# Board_1.net
KiCad netlist of a schematic drawn in EAGLE
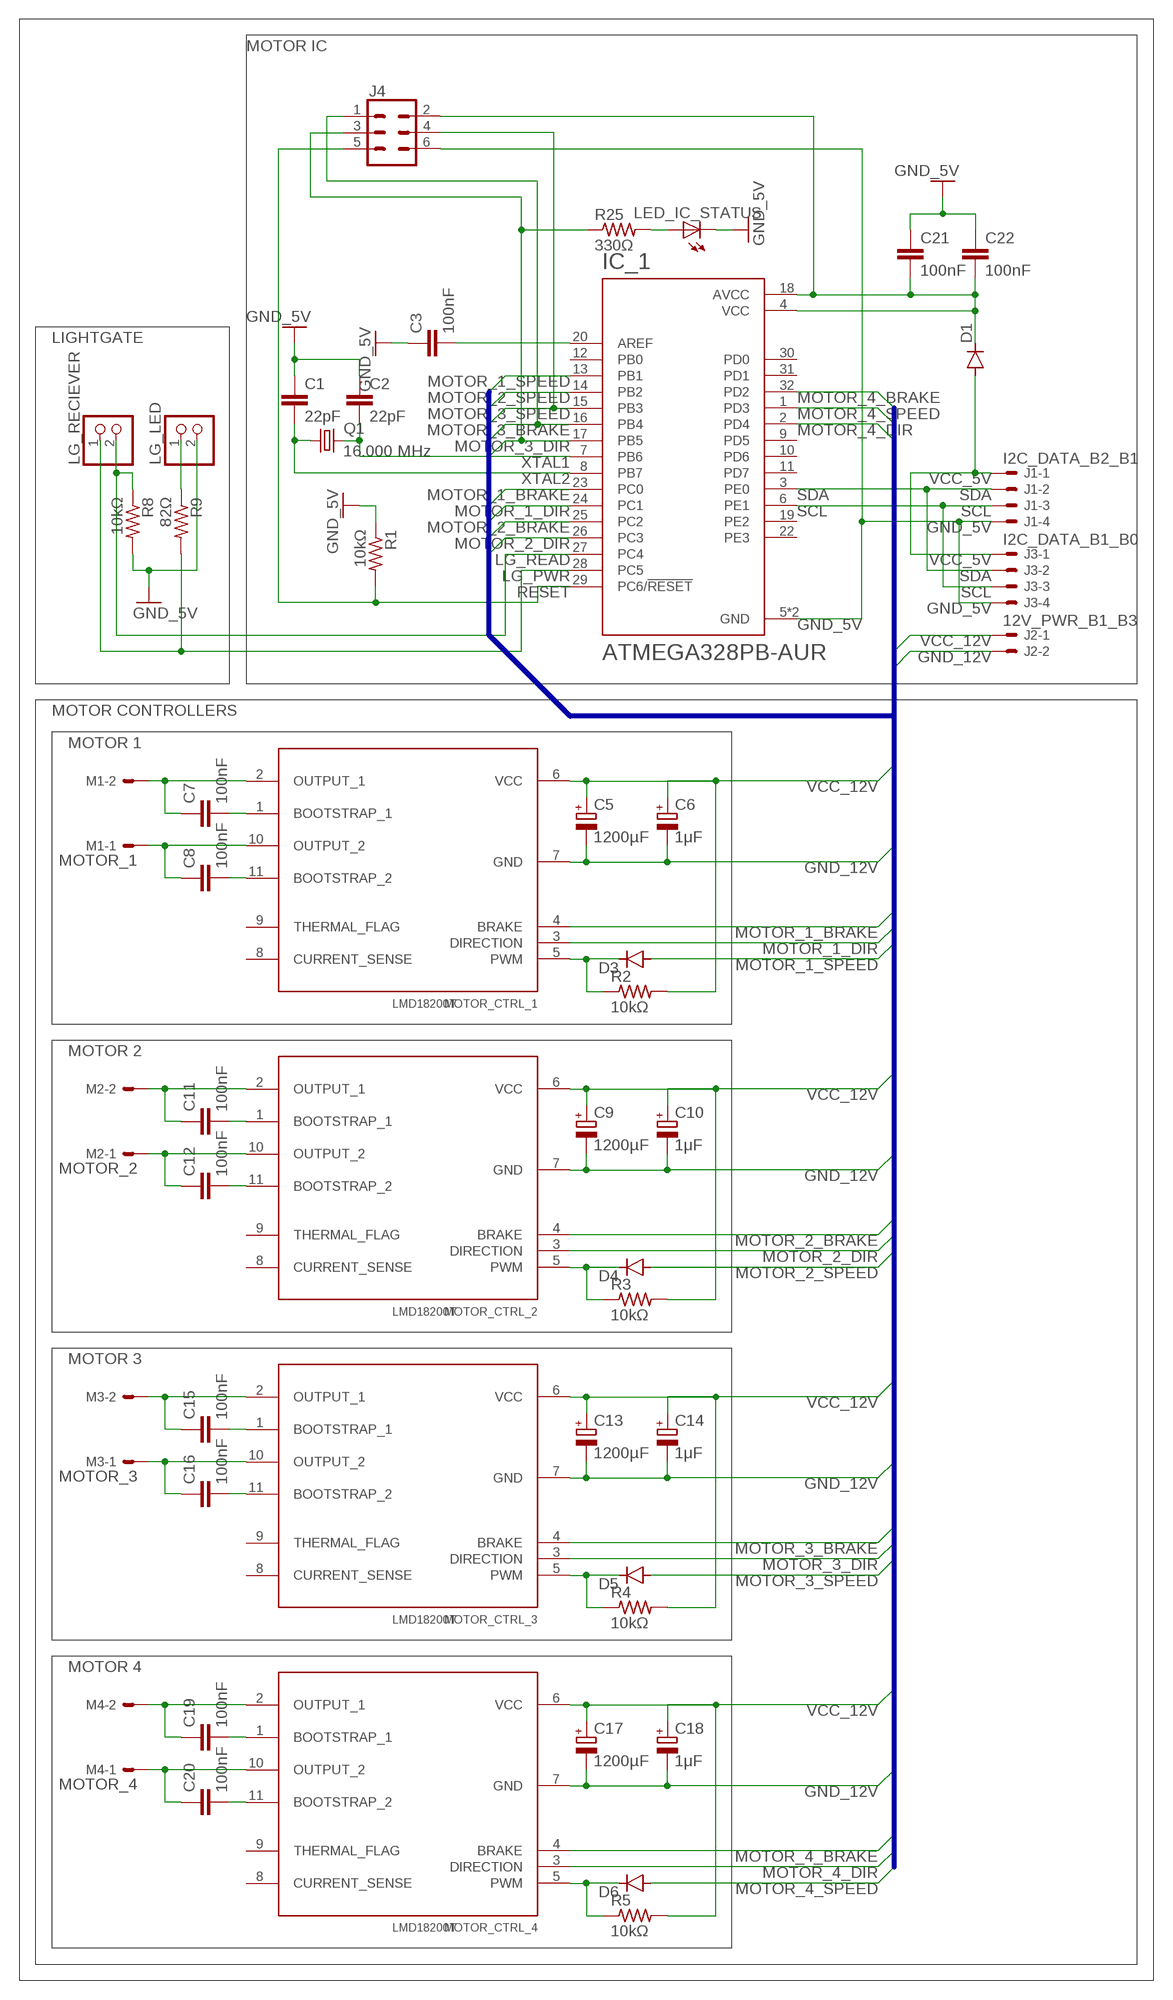
[diagram p0: schematic, sheet 1]

(export (version "E")
  (design (tool "Eeschema 10.0.6"))
  (components
    (comp (ref "C1")
      (value "22pF")
      (footprint "eagle-import:C050-024X044")
      (libsource (lib "eagle-import") (part "C-EU050-024X044"))
    )
    (comp (ref "C2")
      (value "22pF")
      (footprint "eagle-import:C050-024X044")
      (libsource (lib "eagle-import") (part "C-EU050-024X044"))
    )
    (comp (ref "C3")
      (value "100nF")
      (footprint "eagle-import:C050-024X044")
      (libsource (lib "eagle-import") (part "C-EU050-024X044"))
    )
    (comp (ref "C5")
      (value "1200µF")
      (footprint "eagle-import:E5-13")
      (libsource (lib "eagle-import") (part "CPOL-EUE5-13"))
    )
    (comp (ref "C6")
      (value "1μF")
      (footprint "eagle-import:E2-5")
      (libsource (lib "eagle-import") (part "CPOL-EUE2-5"))
    )
    (comp (ref "C7")
      (value "100nF")
      (footprint "eagle-import:C050-024X044")
      (libsource (lib "eagle-import") (part "C-EU050-024X044"))
    )
    (comp (ref "C8")
      (value "100nF")
      (footprint "eagle-import:C050-024X044")
      (libsource (lib "eagle-import") (part "C-EU050-024X044"))
    )
    (comp (ref "C9")
      (value "1200µF")
      (footprint "eagle-import:E5-13")
      (libsource (lib "eagle-import") (part "CPOL-EUE5-13"))
    )
    (comp (ref "C10")
      (value "1μF")
      (footprint "eagle-import:E2-5")
      (libsource (lib "eagle-import") (part "CPOL-EUE2-5"))
    )
    (comp (ref "C11")
      (value "100nF")
      (footprint "eagle-import:C050-024X044")
      (libsource (lib "eagle-import") (part "C-EU050-024X044"))
    )
    (comp (ref "C12")
      (value "100nF")
      (footprint "eagle-import:C050-024X044")
      (libsource (lib "eagle-import") (part "C-EU050-024X044"))
    )
    (comp (ref "C13")
      (value "1200µF")
      (footprint "eagle-import:E5-13")
      (libsource (lib "eagle-import") (part "CPOL-EUE5-13"))
    )
    (comp (ref "C14")
      (value "1μF")
      (footprint "eagle-import:E2-5")
      (libsource (lib "eagle-import") (part "CPOL-EUE2-5"))
    )
    (comp (ref "C15")
      (value "100nF")
      (footprint "eagle-import:C050-024X044")
      (libsource (lib "eagle-import") (part "C-EU050-024X044"))
    )
    (comp (ref "C16")
      (value "100nF")
      (footprint "eagle-import:C050-024X044")
      (libsource (lib "eagle-import") (part "C-EU050-024X044"))
    )
    (comp (ref "C17")
      (value "1200µF")
      (footprint "eagle-import:E5-13")
      (libsource (lib "eagle-import") (part "CPOL-EUE5-13"))
    )
    (comp (ref "C18")
      (value "1μF")
      (footprint "eagle-import:E2-5")
      (libsource (lib "eagle-import") (part "CPOL-EUE2-5"))
    )
    (comp (ref "C19")
      (value "100nF")
      (footprint "eagle-import:C050-024X044")
      (libsource (lib "eagle-import") (part "C-EU050-024X044"))
    )
    (comp (ref "C20")
      (value "100nF")
      (footprint "eagle-import:C050-024X044")
      (libsource (lib "eagle-import") (part "C-EU050-024X044"))
    )
    (comp (ref "C21")
      (value "100nF")
      (footprint "eagle-import:C050-024X044")
      (libsource (lib "eagle-import") (part "C-EU050-024X044"))
    )
    (comp (ref "C22")
      (value "100nF")
      (footprint "eagle-import:C050-024X044")
      (libsource (lib "eagle-import") (part "C-EU050-024X044"))
    )
    (comp (ref "D1")
      (value "1N4148DO35-7")
      (footprint "eagle-import:DO35-7")
      (libsource (lib "eagle-import") (part "1N4148DO35-7"))
    )
    (comp (ref "D3")
      (value "1N4148DO35-7")
      (footprint "eagle-import:DO35-7")
      (libsource (lib "eagle-import") (part "1N4148DO35-7"))
    )
    (comp (ref "D4")
      (value "1N4148DO35-7")
      (footprint "eagle-import:DO35-7")
      (libsource (lib "eagle-import") (part "1N4148DO35-7"))
    )
    (comp (ref "D5")
      (value "1N4148DO35-7")
      (footprint "eagle-import:DO35-7")
      (libsource (lib "eagle-import") (part "1N4148DO35-7"))
    )
    (comp (ref "D6")
      (value "1N4148DO35-7")
      (footprint "eagle-import:DO35-7")
      (libsource (lib "eagle-import") (part "1N4148DO35-7"))
    )
    (comp (ref "IC_1")
      (value "ATMEGA328PB-AUR")
      (footprint "eagle-import:QFP80P900X900X120-32N")
      (fields (field (name "MF") "Microchip"))
      (libsource (lib "eagle-import") (part "ATMEGA328PB-AUR"))
    )
    (comp (ref "J1")
      (value "I2C_DATA_B2_B1")
      (footprint "eagle-import:6410-04")
      (fields (field (name "MF") "MOLEX"))
      (libsource (lib "eagle-import") (part "22-?-0427-2041"))
    )
    (comp (ref "J2")
      (value "12V_PWR_B1_B3")
      (footprint "eagle-import:6410-02")
      (fields (field (name "MF") "MOLEX"))
      (libsource (lib "eagle-import") (part "22-?-0227-2021"))
    )
    (comp (ref "J3")
      (value "I2C_DATA_B1_B0")
      (footprint "eagle-import:6410-04")
      (fields (field (name "MF") "MOLEX"))
      (libsource (lib "eagle-import") (part "22-?-0427-2041"))
    )
    (comp (ref "J4")
      (value "CONN_03X2SHROUD")
      (footprint "eagle-import:2X3-SHROUDED")
      (libsource (lib "eagle-import") (part "CONN_03X2SHROUD"))
    )
    (comp (ref "LED_IC_STATUS")
      (value "LEDP-LCC-2")
      (footprint "eagle-import:P-LCC-2")
      (libsource (lib "eagle-import") (part "LEDP-LCC-2"))
    )
    (comp (ref "LG_LED")
      (value "PINHD-1X2")
      (footprint "eagle-import:1X02")
      (libsource (lib "eagle-import") (part "PINHD-1X2"))
    )
    (comp (ref "LG_RECIEVER")
      (value "PINHD-1X2")
      (footprint "eagle-import:1X02")
      (libsource (lib "eagle-import") (part "PINHD-1X2"))
    )
    (comp (ref "M1")
      (value "MOTOR_1")
      (footprint "eagle-import:6410-02")
      (fields (field (name "MF") "MOLEX"))
      (libsource (lib "eagle-import") (part "22-?-0227-2021"))
    )
    (comp (ref "M2")
      (value "MOTOR_2")
      (footprint "eagle-import:6410-02")
      (fields (field (name "MF") "MOLEX"))
      (libsource (lib "eagle-import") (part "22-?-0227-2021"))
    )
    (comp (ref "M3")
      (value "MOTOR_3")
      (footprint "eagle-import:6410-02")
      (fields (field (name "MF") "MOLEX"))
      (libsource (lib "eagle-import") (part "22-?-0227-2021"))
    )
    (comp (ref "M4")
      (value "MOTOR_4")
      (footprint "eagle-import:6410-02")
      (fields (field (name "MF") "MOLEX"))
      (libsource (lib "eagle-import") (part "22-?-0227-2021"))
    )
    (comp (ref "MOTOR_CTRL_1")
      (value "LMD18200T")
      (footprint "eagle-import:TO-220-11")
      (libsource (lib "eagle-import") (part "LMD18200T"))
    )
    (comp (ref "MOTOR_CTRL_2")
      (value "LMD18200T")
      (footprint "eagle-import:TO-220-11")
      (libsource (lib "eagle-import") (part "LMD18200T"))
    )
    (comp (ref "MOTOR_CTRL_3")
      (value "LMD18200T")
      (footprint "eagle-import:TO-220-11")
      (libsource (lib "eagle-import") (part "LMD18200T"))
    )
    (comp (ref "MOTOR_CTRL_4")
      (value "LMD18200T")
      (footprint "eagle-import:TO-220-11")
      (libsource (lib "eagle-import") (part "LMD18200T"))
    )
    (comp (ref "Q1")
      (value "16.000 MHz")
      (footprint "eagle-import:HC49U-V")
      (libsource (lib "eagle-import") (part "CRYSTALHC49U-V"))
    )
    (comp (ref "R1")
      (value "10kΩ")
      (footprint "eagle-import:0207_10")
      (libsource (lib "eagle-import") (part "R-US_0207/10"))
    )
    (comp (ref "R2")
      (value "10kΩ")
      (footprint "eagle-import:0207_10")
      (libsource (lib "eagle-import") (part "R-US_0207/10"))
    )
    (comp (ref "R3")
      (value "10kΩ")
      (footprint "eagle-import:0207_10")
      (libsource (lib "eagle-import") (part "R-US_0207/10"))
    )
    (comp (ref "R4")
      (value "10kΩ")
      (footprint "eagle-import:0207_10")
      (libsource (lib "eagle-import") (part "R-US_0207/10"))
    )
    (comp (ref "R5")
      (value "10kΩ")
      (footprint "eagle-import:0207_10")
      (libsource (lib "eagle-import") (part "R-US_0207/10"))
    )
    (comp (ref "R8")
      (value "10kΩ")
      (footprint "eagle-import:0207_10")
      (libsource (lib "eagle-import") (part "R-US_0207/10"))
    )
    (comp (ref "R9")
      (value "82Ω")
      (footprint "eagle-import:0207_10")
      (libsource (lib "eagle-import") (part "R-US_0207/10"))
    )
    (comp (ref "R25")
      (value "330Ω")
      (footprint "eagle-import:0207_10")
      (libsource (lib "eagle-import") (part "R-US_0207/10"))
    )
  )
  (nets
    (net (code "1") (name "/GND_12V") (class "Default")
      (node (ref "C10") (pin "-") (pinfunction "-_-") (pintype "passive"))
      (node (ref "C13") (pin "-") (pinfunction "-_-") (pintype "passive"))
      (node (ref "C14") (pin "-") (pinfunction "-_-") (pintype "passive"))
      (node (ref "C17") (pin "-") (pinfunction "-_-") (pintype "passive"))
      (node (ref "C18") (pin "-") (pinfunction "-_-") (pintype "passive"))
      (node (ref "C5") (pin "-") (pinfunction "-_-") (pintype "passive"))
      (node (ref "C6") (pin "-") (pinfunction "-_-") (pintype "passive"))
      (node (ref "C9") (pin "-") (pinfunction "-_-") (pintype "passive"))
      (node (ref "J2") (pin "2") (pinfunction "S_2") (pintype "passive"))
      (node (ref "MOTOR_CTRL_1") (pin "7") (pinfunction "GND_7") (pintype "power_in"))
      (node (ref "MOTOR_CTRL_2") (pin "7") (pinfunction "GND_7") (pintype "power_in"))
      (node (ref "MOTOR_CTRL_3") (pin "7") (pinfunction "GND_7") (pintype "power_in"))
      (node (ref "MOTOR_CTRL_4") (pin "7") (pinfunction "GND_7") (pintype "power_in"))
    )
    (net (code "2") (name "/LG_PWR") (class "Default")
      (node (ref "IC_1") (pin "28") (pinfunction "PC5_28") (pintype "bidirectional"))
      (node (ref "LG_RECIEVER") (pin "1") (pinfunction "1_1") (pintype "passive"))
      (node (ref "R9") (pin "2") (pinfunction "2_2") (pintype "passive"))
    )
    (net (code "3") (name "/LG_READ") (class "Default")
      (node (ref "IC_1") (pin "27") (pinfunction "PC4_27") (pintype "bidirectional"))
      (node (ref "LG_RECIEVER") (pin "2") (pinfunction "2_2") (pintype "passive"))
      (node (ref "R8") (pin "1") (pinfunction "1_1") (pintype "passive"))
    )
    (net (code "4") (name "/MOTOR_1_BRAKE") (class "Default")
      (node (ref "IC_1") (pin "23") (pinfunction "PC0_23") (pintype "bidirectional"))
      (node (ref "MOTOR_CTRL_1") (pin "4") (pinfunction "BRAKE_4") (pintype "input"))
    )
    (net (code "5") (name "/MOTOR_1_DIR") (class "Default")
      (node (ref "IC_1") (pin "24") (pinfunction "PC1_24") (pintype "bidirectional"))
      (node (ref "MOTOR_CTRL_1") (pin "3") (pinfunction "DIRECTION_3") (pintype "input"))
    )
    (net (code "6") (name "/MOTOR_1_SPEED") (class "Default")
      (node (ref "D3") (pin "A") (pinfunction "A_A") (pintype "passive"))
      (node (ref "IC_1") (pin "13") (pinfunction "PB1_13") (pintype "bidirectional"))
    )
    (net (code "7") (name "/MOTOR_2_BRAKE") (class "Default")
      (node (ref "IC_1") (pin "25") (pinfunction "PC2_25") (pintype "bidirectional"))
      (node (ref "MOTOR_CTRL_2") (pin "4") (pinfunction "BRAKE_4") (pintype "input"))
    )
    (net (code "8") (name "/MOTOR_2_DIR") (class "Default")
      (node (ref "IC_1") (pin "26") (pinfunction "PC3_26") (pintype "bidirectional"))
      (node (ref "MOTOR_CTRL_2") (pin "3") (pinfunction "DIRECTION_3") (pintype "input"))
    )
    (net (code "9") (name "/MOTOR_2_SPEED") (class "Default")
      (node (ref "D4") (pin "A") (pinfunction "A_A") (pintype "passive"))
      (node (ref "IC_1") (pin "14") (pinfunction "PB2_14") (pintype "bidirectional"))
    )
    (net (code "10") (name "/MOTOR_3_BRAKE") (class "Default")
      (node (ref "IC_1") (pin "16") (pinfunction "PB4_16") (pintype "bidirectional"))
      (node (ref "J4") (pin "1") (pinfunction "1_1") (pintype "bidirectional"))
      (node (ref "MOTOR_CTRL_3") (pin "4") (pinfunction "BRAKE_4") (pintype "input"))
    )
    (net (code "11") (name "/MOTOR_3_DIR") (class "Default")
      (node (ref "IC_1") (pin "17") (pinfunction "PB5_17") (pintype "bidirectional"))
      (node (ref "J4") (pin "3") (pinfunction "3_3") (pintype "bidirectional"))
      (node (ref "MOTOR_CTRL_3") (pin "3") (pinfunction "DIRECTION_3") (pintype "input"))
      (node (ref "R25") (pin "1") (pinfunction "1_1") (pintype "passive"))
    )
    (net (code "12") (name "/MOTOR_3_SPEED") (class "Default")
      (node (ref "D5") (pin "A") (pinfunction "A_A") (pintype "passive"))
      (node (ref "IC_1") (pin "15") (pinfunction "PB3_15") (pintype "bidirectional"))
      (node (ref "J4") (pin "4") (pinfunction "4_4") (pintype "bidirectional"))
    )
    (net (code "13") (name "/MOTOR_4_BRAKE") (class "Default")
      (node (ref "IC_1") (pin "32") (pinfunction "PD2_32") (pintype "bidirectional"))
      (node (ref "MOTOR_CTRL_4") (pin "4") (pinfunction "BRAKE_4") (pintype "input"))
    )
    (net (code "14") (name "/MOTOR_4_DIR") (class "Default")
      (node (ref "IC_1") (pin "2") (pinfunction "PD4_2") (pintype "bidirectional"))
      (node (ref "MOTOR_CTRL_4") (pin "3") (pinfunction "DIRECTION_3") (pintype "input"))
    )
    (net (code "15") (name "/MOTOR_4_SPEED") (class "Default")
      (node (ref "D6") (pin "A") (pinfunction "A_A") (pintype "passive"))
      (node (ref "IC_1") (pin "1") (pinfunction "PD3_1") (pintype "bidirectional"))
    )
    (net (code "16") (name "/RESET") (class "Default")
      (node (ref "IC_1") (pin "29") (pinfunction "PC6/~{RESET}_29") (pintype "bidirectional"))
      (node (ref "J4") (pin "5") (pinfunction "5_5") (pintype "bidirectional"))
      (node (ref "R1") (pin "2") (pinfunction "2_2") (pintype "passive"))
    )
    (net (code "17") (name "/SCL") (class "Default")
      (node (ref "IC_1") (pin "6") (pinfunction "PE1_6") (pintype "bidirectional"))
      (node (ref "J1") (pin "3") (pinfunction "S_3") (pintype "passive"))
      (node (ref "J3") (pin "3") (pinfunction "S_3") (pintype "passive"))
    )
    (net (code "18") (name "/SDA") (class "Default")
      (node (ref "IC_1") (pin "3") (pinfunction "PE0_3") (pintype "bidirectional"))
      (node (ref "J1") (pin "2") (pinfunction "S_2") (pintype "passive"))
      (node (ref "J3") (pin "2") (pinfunction "S_2") (pintype "passive"))
    )
    (net (code "19") (name "/VCC_5V") (class "Default")
      (node (ref "D1") (pin "A") (pinfunction "A_A") (pintype "passive"))
      (node (ref "J1") (pin "1") (pinfunction "S_1") (pintype "passive"))
      (node (ref "J3") (pin "1") (pinfunction "S_1") (pintype "passive"))
    )
    (net (code "20") (name "/VCC_12V") (class "Default")
      (node (ref "C10") (pin "+") (pinfunction "+_+") (pintype "passive"))
      (node (ref "C13") (pin "+") (pinfunction "+_+") (pintype "passive"))
      (node (ref "C14") (pin "+") (pinfunction "+_+") (pintype "passive"))
      (node (ref "C17") (pin "+") (pinfunction "+_+") (pintype "passive"))
      (node (ref "C18") (pin "+") (pinfunction "+_+") (pintype "passive"))
      (node (ref "C5") (pin "+") (pinfunction "+_+") (pintype "passive"))
      (node (ref "C6") (pin "+") (pinfunction "+_+") (pintype "passive"))
      (node (ref "C9") (pin "+") (pinfunction "+_+") (pintype "passive"))
      (node (ref "J2") (pin "1") (pinfunction "S_1") (pintype "passive"))
      (node (ref "MOTOR_CTRL_1") (pin "6") (pinfunction "VCC_6") (pintype "power_in"))
      (node (ref "MOTOR_CTRL_2") (pin "6") (pinfunction "VCC_6") (pintype "power_in"))
      (node (ref "MOTOR_CTRL_3") (pin "6") (pinfunction "VCC_6") (pintype "power_in"))
      (node (ref "MOTOR_CTRL_4") (pin "6") (pinfunction "VCC_6") (pintype "power_in"))
      (node (ref "R2") (pin "2") (pinfunction "2_2") (pintype "passive"))
      (node (ref "R3") (pin "2") (pinfunction "2_2") (pintype "passive"))
      (node (ref "R4") (pin "2") (pinfunction "2_2") (pintype "passive"))
      (node (ref "R5") (pin "2") (pinfunction "2_2") (pintype "passive"))
    )
    (net (code "21") (name "/XTAL1") (class "Default")
      (node (ref "C2") (pin "2") (pinfunction "2_2") (pintype "passive"))
      (node (ref "IC_1") (pin "7") (pinfunction "PB6_7") (pintype "bidirectional"))
      (node (ref "Q1") (pin "2") (pinfunction "2_2") (pintype "passive"))
    )
    (net (code "22") (name "/XTAL2") (class "Default")
      (node (ref "C1") (pin "2") (pinfunction "2_2") (pintype "passive"))
      (node (ref "IC_1") (pin "8") (pinfunction "PB7_8") (pintype "bidirectional"))
      (node (ref "Q1") (pin "1") (pinfunction "1_1") (pintype "passive"))
    )
    (net (code "23") (name "GND_5V") (class "Default")
      (node (ref "C1") (pin "1") (pinfunction "1_1") (pintype "passive"))
      (node (ref "C2") (pin "1") (pinfunction "1_1") (pintype "passive"))
      (node (ref "C21") (pin "1") (pinfunction "1_1") (pintype "passive"))
      (node (ref "C22") (pin "1") (pinfunction "1_1") (pintype "passive"))
      (node (ref "C3") (pin "1") (pinfunction "1_1") (pintype "passive"))
      (node (ref "IC_1") (pin "21") (pinfunction "GND_21") (pintype "power_in"))
      (node (ref "IC_1") (pin "5") (pinfunction "GND_5") (pintype "power_in"))
      (node (ref "J1") (pin "4") (pinfunction "S_4") (pintype "passive"))
      (node (ref "J3") (pin "4") (pinfunction "S_4") (pintype "passive"))
      (node (ref "J4") (pin "6") (pinfunction "6_6") (pintype "bidirectional"))
      (node (ref "LED_IC_STATUS") (pin "C") (pinfunction "C_C") (pintype "passive"))
      (node (ref "LG_LED") (pin "2") (pinfunction "2_2") (pintype "passive"))
      (node (ref "R1") (pin "1") (pinfunction "1_1") (pintype "passive"))
      (node (ref "R8") (pin "2") (pinfunction "2_2") (pintype "passive"))
    )
    (net (code "24") (name "Net-(IC_1-AREF)") (class "Default")
      (node (ref "C3") (pin "2") (pinfunction "2_2") (pintype "passive"))
      (node (ref "IC_1") (pin "20") (pinfunction "AREF_20") (pintype "input"))
    )
    (net (code "25") (name "Net-(IC_1-AVCC)") (class "Default")
      (node (ref "C21") (pin "2") (pinfunction "2_2") (pintype "passive"))
      (node (ref "C22") (pin "2") (pinfunction "2_2") (pintype "passive"))
      (node (ref "D1") (pin "C") (pinfunction "C_C") (pintype "passive"))
      (node (ref "IC_1") (pin "18") (pinfunction "AVCC_18") (pintype "power_in"))
      (node (ref "IC_1") (pin "4") (pinfunction "VCC_4") (pintype "power_in"))
      (node (ref "J4") (pin "2") (pinfunction "2_2") (pintype "bidirectional"))
    )
    (net (code "26") (name "Net-(LED_IC_STATUS-PadA)") (class "Default")
      (node (ref "LED_IC_STATUS") (pin "A") (pinfunction "A_A") (pintype "passive"))
      (node (ref "R25") (pin "2") (pinfunction "2_2") (pintype "passive"))
    )
    (net (code "27") (name "Net-(LG_LED-Pad1)") (class "Default")
      (node (ref "LG_LED") (pin "1") (pinfunction "1_1") (pintype "passive"))
      (node (ref "R9") (pin "1") (pinfunction "1_1") (pintype "passive"))
    )
    (net (code "28") (name "Net-(M1A-S)") (class "Default")
      (node (ref "C8") (pin "1") (pinfunction "1_1") (pintype "passive"))
      (node (ref "M1") (pin "1") (pinfunction "S_1") (pintype "passive"))
      (node (ref "MOTOR_CTRL_1") (pin "10") (pinfunction "OUTPUT_2_10") (pintype "output"))
    )
    (net (code "29") (name "Net-(M1B-S)") (class "Default")
      (node (ref "C7") (pin "1") (pinfunction "1_1") (pintype "passive"))
      (node (ref "M1") (pin "2") (pinfunction "S_2") (pintype "passive"))
      (node (ref "MOTOR_CTRL_1") (pin "2") (pinfunction "OUTPUT_1_2") (pintype "output"))
    )
    (net (code "30") (name "Net-(M2A-S)") (class "Default")
      (node (ref "C12") (pin "1") (pinfunction "1_1") (pintype "passive"))
      (node (ref "M2") (pin "1") (pinfunction "S_1") (pintype "passive"))
      (node (ref "MOTOR_CTRL_2") (pin "10") (pinfunction "OUTPUT_2_10") (pintype "output"))
    )
    (net (code "31") (name "Net-(M2B-S)") (class "Default")
      (node (ref "C11") (pin "1") (pinfunction "1_1") (pintype "passive"))
      (node (ref "M2") (pin "2") (pinfunction "S_2") (pintype "passive"))
      (node (ref "MOTOR_CTRL_2") (pin "2") (pinfunction "OUTPUT_1_2") (pintype "output"))
    )
    (net (code "32") (name "Net-(M3A-S)") (class "Default")
      (node (ref "C16") (pin "1") (pinfunction "1_1") (pintype "passive"))
      (node (ref "M3") (pin "1") (pinfunction "S_1") (pintype "passive"))
      (node (ref "MOTOR_CTRL_3") (pin "10") (pinfunction "OUTPUT_2_10") (pintype "output"))
    )
    (net (code "33") (name "Net-(M3B-S)") (class "Default")
      (node (ref "C15") (pin "1") (pinfunction "1_1") (pintype "passive"))
      (node (ref "M3") (pin "2") (pinfunction "S_2") (pintype "passive"))
      (node (ref "MOTOR_CTRL_3") (pin "2") (pinfunction "OUTPUT_1_2") (pintype "output"))
    )
    (net (code "34") (name "Net-(M4A-S)") (class "Default")
      (node (ref "C20") (pin "1") (pinfunction "1_1") (pintype "passive"))
      (node (ref "M4") (pin "1") (pinfunction "S_1") (pintype "passive"))
      (node (ref "MOTOR_CTRL_4") (pin "10") (pinfunction "OUTPUT_2_10") (pintype "output"))
    )
    (net (code "35") (name "Net-(M4B-S)") (class "Default")
      (node (ref "C19") (pin "1") (pinfunction "1_1") (pintype "passive"))
      (node (ref "M4") (pin "2") (pinfunction "S_2") (pintype "passive"))
      (node (ref "MOTOR_CTRL_4") (pin "2") (pinfunction "OUTPUT_1_2") (pintype "output"))
    )
    (net (code "36") (name "Net-(MOTOR_CTRL_1-BOOTSTRAP_1)") (class "Default")
      (node (ref "C7") (pin "2") (pinfunction "2_2") (pintype "passive"))
      (node (ref "MOTOR_CTRL_1") (pin "1") (pinfunction "BOOTSTRAP_1_1") (pintype "output"))
    )
    (net (code "37") (name "Net-(MOTOR_CTRL_1-BOOTSTRAP_2)") (class "Default")
      (node (ref "C8") (pin "2") (pinfunction "2_2") (pintype "passive"))
      (node (ref "MOTOR_CTRL_1") (pin "11") (pinfunction "BOOTSTRAP_2_11") (pintype "output"))
    )
    (net (code "38") (name "Net-(MOTOR_CTRL_1-PWM)") (class "Default")
      (node (ref "D3") (pin "C") (pinfunction "C_C") (pintype "passive"))
      (node (ref "MOTOR_CTRL_1") (pin "5") (pinfunction "PWM_5") (pintype "input"))
      (node (ref "R2") (pin "1") (pinfunction "1_1") (pintype "passive"))
    )
    (net (code "39") (name "Net-(MOTOR_CTRL_2-BOOTSTRAP_1)") (class "Default")
      (node (ref "C11") (pin "2") (pinfunction "2_2") (pintype "passive"))
      (node (ref "MOTOR_CTRL_2") (pin "1") (pinfunction "BOOTSTRAP_1_1") (pintype "output"))
    )
    (net (code "40") (name "Net-(MOTOR_CTRL_2-BOOTSTRAP_2)") (class "Default")
      (node (ref "C12") (pin "2") (pinfunction "2_2") (pintype "passive"))
      (node (ref "MOTOR_CTRL_2") (pin "11") (pinfunction "BOOTSTRAP_2_11") (pintype "output"))
    )
    (net (code "41") (name "Net-(MOTOR_CTRL_2-PWM)") (class "Default")
      (node (ref "D4") (pin "C") (pinfunction "C_C") (pintype "passive"))
      (node (ref "MOTOR_CTRL_2") (pin "5") (pinfunction "PWM_5") (pintype "input"))
      (node (ref "R3") (pin "1") (pinfunction "1_1") (pintype "passive"))
    )
    (net (code "42") (name "Net-(MOTOR_CTRL_3-BOOTSTRAP_1)") (class "Default")
      (node (ref "C15") (pin "2") (pinfunction "2_2") (pintype "passive"))
      (node (ref "MOTOR_CTRL_3") (pin "1") (pinfunction "BOOTSTRAP_1_1") (pintype "output"))
    )
    (net (code "43") (name "Net-(MOTOR_CTRL_3-BOOTSTRAP_2)") (class "Default")
      (node (ref "C16") (pin "2") (pinfunction "2_2") (pintype "passive"))
      (node (ref "MOTOR_CTRL_3") (pin "11") (pinfunction "BOOTSTRAP_2_11") (pintype "output"))
    )
    (net (code "44") (name "Net-(MOTOR_CTRL_3-PWM)") (class "Default")
      (node (ref "D5") (pin "C") (pinfunction "C_C") (pintype "passive"))
      (node (ref "MOTOR_CTRL_3") (pin "5") (pinfunction "PWM_5") (pintype "input"))
      (node (ref "R4") (pin "1") (pinfunction "1_1") (pintype "passive"))
    )
    (net (code "45") (name "Net-(MOTOR_CTRL_4-BOOTSTRAP_1)") (class "Default")
      (node (ref "C19") (pin "2") (pinfunction "2_2") (pintype "passive"))
      (node (ref "MOTOR_CTRL_4") (pin "1") (pinfunction "BOOTSTRAP_1_1") (pintype "output"))
    )
    (net (code "46") (name "Net-(MOTOR_CTRL_4-BOOTSTRAP_2)") (class "Default")
      (node (ref "C20") (pin "2") (pinfunction "2_2") (pintype "passive"))
      (node (ref "MOTOR_CTRL_4") (pin "11") (pinfunction "BOOTSTRAP_2_11") (pintype "output"))
    )
    (net (code "47") (name "Net-(MOTOR_CTRL_4-PWM)") (class "Default")
      (node (ref "D6") (pin "C") (pinfunction "C_C") (pintype "passive"))
      (node (ref "MOTOR_CTRL_4") (pin "5") (pinfunction "PWM_5") (pintype "input"))
      (node (ref "R5") (pin "1") (pinfunction "1_1") (pintype "passive"))
    )
    (net (code "48") (name "unconnected-(IC_1-PB0-Pad12)") (class "Default")
      (node (ref "IC_1") (pin "12") (pinfunction "PB0_12") (pintype "bidirectional"))
    )
    (net (code "49") (name "unconnected-(IC_1-PD0-Pad30)") (class "Default")
      (node (ref "IC_1") (pin "30") (pinfunction "PD0_30") (pintype "bidirectional"))
    )
    (net (code "50") (name "unconnected-(IC_1-PD1-Pad31)") (class "Default")
      (node (ref "IC_1") (pin "31") (pinfunction "PD1_31") (pintype "bidirectional"))
    )
    (net (code "51") (name "unconnected-(IC_1-PD5-Pad9)") (class "Default")
      (node (ref "IC_1") (pin "9") (pinfunction "PD5_9") (pintype "bidirectional"))
    )
    (net (code "52") (name "unconnected-(IC_1-PD6-Pad10)") (class "Default")
      (node (ref "IC_1") (pin "10") (pinfunction "PD6_10") (pintype "bidirectional"))
    )
    (net (code "53") (name "unconnected-(IC_1-PD7-Pad11)") (class "Default")
      (node (ref "IC_1") (pin "11") (pinfunction "PD7_11") (pintype "bidirectional"))
    )
    (net (code "54") (name "unconnected-(IC_1-PE2-Pad19)") (class "Default")
      (node (ref "IC_1") (pin "19") (pinfunction "PE2_19") (pintype "bidirectional"))
    )
    (net (code "55") (name "unconnected-(IC_1-PE3-Pad22)") (class "Default")
      (node (ref "IC_1") (pin "22") (pinfunction "PE3_22") (pintype "bidirectional"))
    )
    (net (code "56") (name "unconnected-(MOTOR_CTRL_1-CURRENT_SENSE-Pad8)") (class "Default")
      (node (ref "MOTOR_CTRL_1") (pin "8") (pinfunction "CURRENT_SENSE_8") (pintype "output"))
    )
    (net (code "57") (name "unconnected-(MOTOR_CTRL_1-THERMAL_FLAG-Pad9)") (class "Default")
      (node (ref "MOTOR_CTRL_1") (pin "9") (pinfunction "THERMAL_FLAG_9") (pintype "output"))
    )
    (net (code "58") (name "unconnected-(MOTOR_CTRL_2-CURRENT_SENSE-Pad8)") (class "Default")
      (node (ref "MOTOR_CTRL_2") (pin "8") (pinfunction "CURRENT_SENSE_8") (pintype "output"))
    )
    (net (code "59") (name "unconnected-(MOTOR_CTRL_2-THERMAL_FLAG-Pad9)") (class "Default")
      (node (ref "MOTOR_CTRL_2") (pin "9") (pinfunction "THERMAL_FLAG_9") (pintype "output"))
    )
    (net (code "60") (name "unconnected-(MOTOR_CTRL_3-CURRENT_SENSE-Pad8)") (class "Default")
      (node (ref "MOTOR_CTRL_3") (pin "8") (pinfunction "CURRENT_SENSE_8") (pintype "output"))
    )
    (net (code "61") (name "unconnected-(MOTOR_CTRL_3-THERMAL_FLAG-Pad9)") (class "Default")
      (node (ref "MOTOR_CTRL_3") (pin "9") (pinfunction "THERMAL_FLAG_9") (pintype "output"))
    )
    (net (code "62") (name "unconnected-(MOTOR_CTRL_4-CURRENT_SENSE-Pad8)") (class "Default")
      (node (ref "MOTOR_CTRL_4") (pin "8") (pinfunction "CURRENT_SENSE_8") (pintype "output"))
    )
    (net (code "63") (name "unconnected-(MOTOR_CTRL_4-THERMAL_FLAG-Pad9)") (class "Default")
      (node (ref "MOTOR_CTRL_4") (pin "9") (pinfunction "THERMAL_FLAG_9") (pintype "output"))
    )
  )
)
